# ECAT_SWITCH.net
KiCad netlist of a schematic drawn in Altium Designer
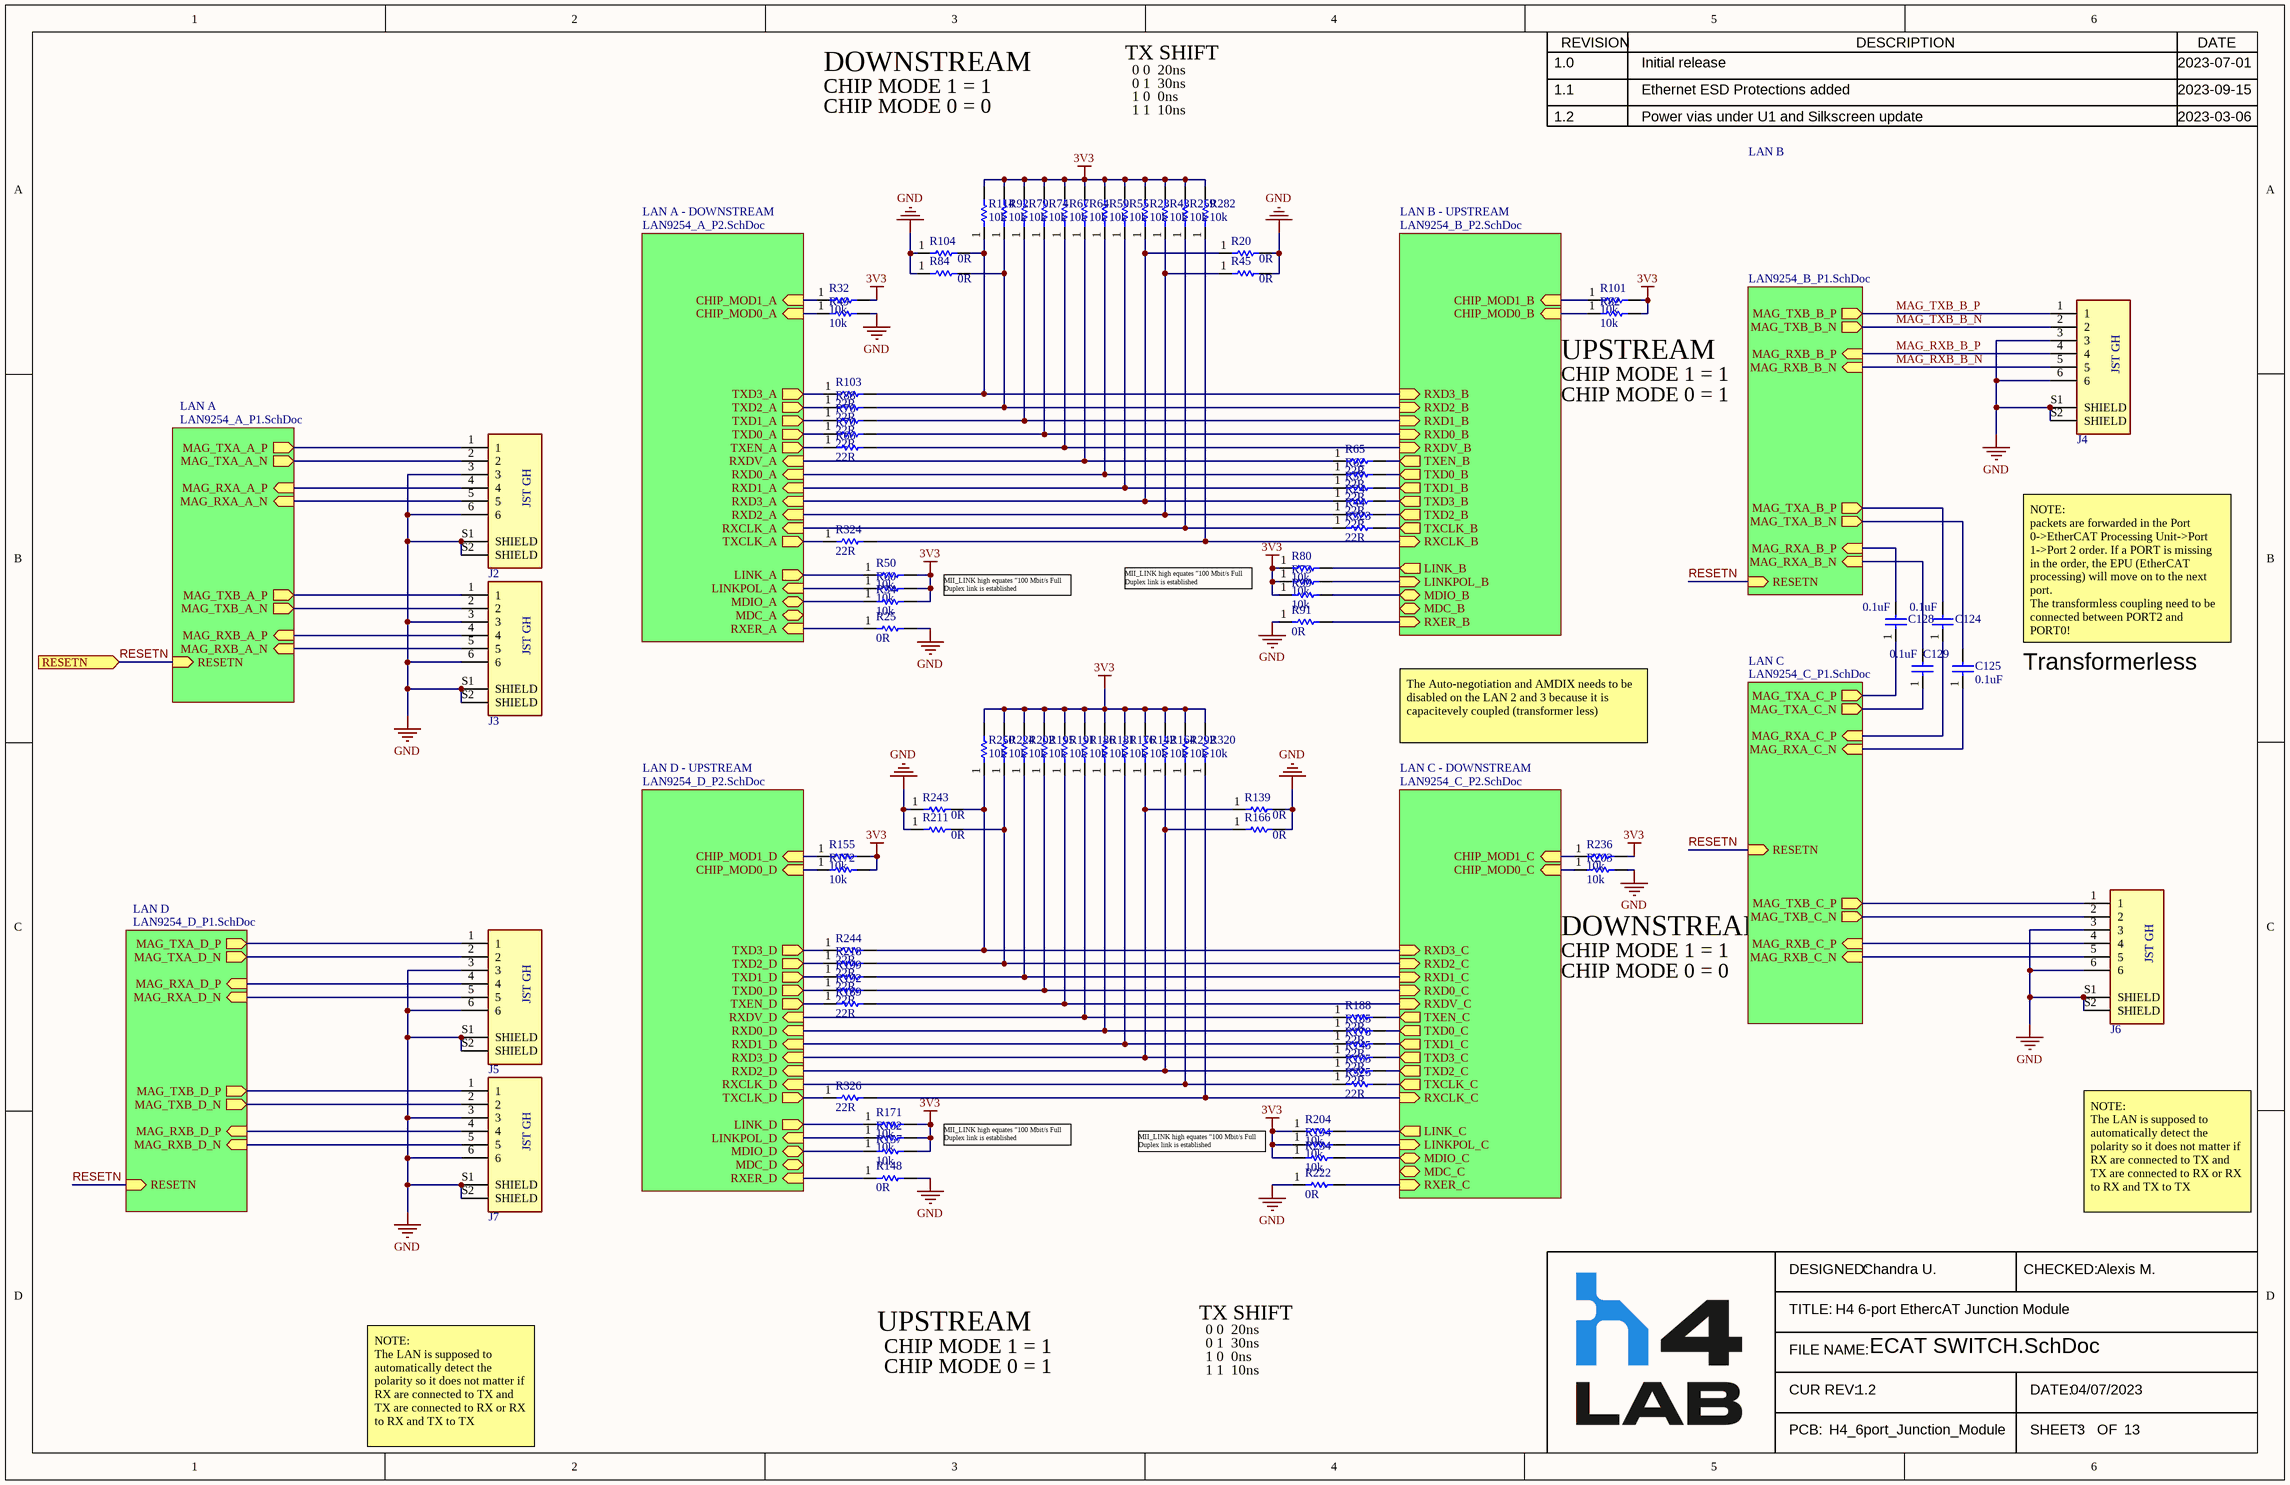
[diagram p0: ECAT SWITCH.SchDoc]

(export (version "E")
  (design (tool "Eeschema 10.0.6"))
  (components
    (comp (ref "C124")
      (value "0.1uF")
      (footprint "CAPC1608X09N(0603)")
      (description "CAP CER 0.1UF 100V X7R 0603")
      (fields (field (name "MPN") "CL10B104KC8NNNC") (field (name "TOLERANCE") "10%"))
      (libsource (lib "IHMC_Altium_Lib") (part "0.1uF_100V_0603_CAP"))
    )
    (comp (ref "C125")
      (value "0.1uF")
      (footprint "CAPC1608X09N(0603)")
      (description "CAP CER 0.1UF 100V X7R 0603")
      (fields (field (name "MPN") "CL10B104KC8NNNC") (field (name "TOLERANCE") "10%"))
      (libsource (lib "IHMC_Altium_Lib") (part "0.1uF_100V_0603_CAP"))
    )
    (comp (ref "C128")
      (value "0.1uF")
      (footprint "CAPC1608X09N(0603)")
      (description "CAP CER 0.1UF 100V X7R 0603")
      (fields (field (name "MPN") "CL10B104KC8NNNC") (field (name "TOLERANCE") "10%"))
      (libsource (lib "IHMC_Altium_Lib") (part "0.1uF_100V_0603_CAP"))
    )
    (comp (ref "C129")
      (value "0.1uF")
      (footprint "CAPC1608X09N(0603)")
      (description "CAP CER 0.1UF 100V X7R 0603")
      (fields (field (name "MPN") "CL10B104KC8NNNC") (field (name "TOLERANCE") "10%"))
      (libsource (lib "IHMC_Altium_Lib") (part "0.1uF_100V_0603_CAP"))
    )
    (comp (ref "J2")
      (value "BM06B-GHS-TBT")
      (footprint "JST_GH_6POS_STRAI")
      (description "CONN HEADER GH TOP 6POS 1.25MM")
      (fields
        (field (name "MANUFACTURER") "JST")
        (field (name "MANUFACTURER PART NUMBER") "BM06B-GHS-TBT(LF)(SN)(N)")
      )
      (libsource (lib "IHMC_Altium_Lib") (part "BM06B-GHS-TBT_JST_6POS_1.25MM_CON"))
    )
    (comp (ref "J3")
      (value "BM06B-GHS-TBT")
      (footprint "JST_GH_6POS_STRAI")
      (description "CONN HEADER GH TOP 6POS 1.25MM")
      (fields
        (field (name "MANUFACTURER") "JST")
        (field (name "MANUFACTURER PART NUMBER") "BM06B-GHS-TBT(LF)(SN)(N)")
      )
      (libsource (lib "IHMC_Altium_Lib") (part "BM06B-GHS-TBT_JST_6POS_1.25MM_CON"))
    )
    (comp (ref "J4")
      (value "BM06B-GHS-TBT")
      (footprint "JST_GH_6POS_STRAI")
      (description "CONN HEADER GH TOP 6POS 1.25MM")
      (fields
        (field (name "MANUFACTURER") "JST")
        (field (name "MANUFACTURER PART NUMBER") "BM06B-GHS-TBT(LF)(SN)(N)")
      )
      (libsource (lib "IHMC_Altium_Lib") (part "BM06B-GHS-TBT_JST_6POS_1.25MM_CON"))
    )
    (comp (ref "J5")
      (value "BM06B-GHS-TBT")
      (footprint "JST_GH_6POS_STRAI")
      (description "CONN HEADER GH TOP 6POS 1.25MM")
      (fields
        (field (name "MANUFACTURER") "JST")
        (field (name "MANUFACTURER PART NUMBER") "BM06B-GHS-TBT(LF)(SN)(N)")
      )
      (libsource (lib "IHMC_Altium_Lib") (part "BM06B-GHS-TBT_JST_6POS_1.25MM_CON"))
    )
    (comp (ref "J6")
      (value "BM06B-GHS-TBT")
      (footprint "JST_GH_6POS_STRAI")
      (description "CONN HEADER GH TOP 6POS 1.25MM")
      (fields
        (field (name "MANUFACTURER") "JST")
        (field (name "MANUFACTURER PART NUMBER") "BM06B-GHS-TBT(LF)(SN)(N)")
      )
      (libsource (lib "IHMC_Altium_Lib") (part "BM06B-GHS-TBT_JST_6POS_1.25MM_CON"))
    )
    (comp (ref "J7")
      (value "BM06B-GHS-TBT")
      (footprint "JST_GH_6POS_STRAI")
      (description "CONN HEADER GH TOP 6POS 1.25MM")
      (fields
        (field (name "MANUFACTURER") "JST")
        (field (name "MANUFACTURER PART NUMBER") "BM06B-GHS-TBT(LF)(SN)(N)")
      )
      (libsource (lib "IHMC_Altium_Lib") (part "BM06B-GHS-TBT_JST_6POS_1.25MM_CON"))
    )
    (comp (ref "R20")
      (value "0R")
      (footprint "RESC1608X09N(0603)")
      (description "RES SMD 0 OHM JUMPER 1/10W 0603")
      (fields (field (name "MPN") "RC0603JR-070RL") (field (name "TOLERANCE") "Jumper"))
      (libsource (lib "H4_6-port_EtherCAT_Junction_Module") (part "0R_1/10W_0603_RES"))
    )
    (comp (ref "R23")
      (value "10k")
      (footprint "RESC1005X06N(0402)")
      (description "RES SMD 10K OHM 1% 1/16W 0402")
      (fields (field (name "MPN") "RC0402FR-0710KL") (field (name "TOLERANCE") "1%"))
      (libsource (lib "IHMC_Resistors") (part "10k_1/16W_0402_RES"))
    )
    (comp (ref "R24")
      (value "22R")
      (footprint "0402")
      (description "Res Thick Film 0402 22 Ohm 1% 0.125W(1/8W) ±200ppm/C Pad SMD T/R")
      (fields
        (field (name "MANUFACTURER") "TE Connectivity")
        (field (name "MANUFACTURER PART NUMBER") "CRGP0402F22R")
      )
      (libsource (lib "IHMC_Resistors") (part "22R_1/8W_1%_0402_CRGP0402F22R_RES"))
    )
    (comp (ref "R25")
      (value "0R")
      (footprint "0402")
      (fields
        (field (name "MANUFACTURER") "Vishay Dale")
        (field (name "MANUFACTURER PART NUMBER") "RCS04020000Z0ED")
      )
      (libsource (lib "IHMC_Altium_Lib") (part "0R_1/5W_0402_RCS04020000Z0ED_RES"))
    )
    (comp (ref "R32")
      (value "10k")
      (footprint "RESC1005X06N(0402)")
      (description "RES SMD 10K OHM 1% 1/16W 0402")
      (fields (field (name "MPN") "RC0402FR-0710KL") (field (name "TOLERANCE") "1%"))
      (libsource (lib "IHMC_Resistors") (part "10k_1/16W_0402_RES"))
    )
    (comp (ref "R34")
      (value "10k")
      (footprint "RESC1005X06N(0402)")
      (description "RES SMD 10K OHM 1% 1/16W 0402")
      (fields (field (name "MPN") "RC0402FR-0710KL") (field (name "TOLERANCE") "1%"))
      (libsource (lib "IHMC_Resistors") (part "10k_1/16W_0402_RES"))
    )
    (comp (ref "R43")
      (value "10k")
      (footprint "RESC1005X06N(0402)")
      (description "RES SMD 10K OHM 1% 1/16W 0402")
      (fields (field (name "MPN") "RC0402FR-0710KL") (field (name "TOLERANCE") "1%"))
      (libsource (lib "IHMC_Resistors") (part "10k_1/16W_0402_RES"))
    )
    (comp (ref "R44")
      (value "22R")
      (footprint "0402")
      (description "Res Thick Film 0402 22 Ohm 1% 0.125W(1/8W) ±200ppm/C Pad SMD T/R")
      (fields
        (field (name "MANUFACTURER") "TE Connectivity")
        (field (name "MANUFACTURER PART NUMBER") "CRGP0402F22R")
      )
      (libsource (lib "IHMC_Resistors") (part "22R_1/8W_1%_0402_CRGP0402F22R_RES"))
    )
    (comp (ref "R45")
      (value "0R")
      (footprint "RESC1608X09N(0603)")
      (description "RES SMD 0 OHM JUMPER 1/10W 0603")
      (fields (field (name "MPN") "RC0603JR-070RL") (field (name "TOLERANCE") "Jumper"))
      (libsource (lib "H4_6-port_EtherCAT_Junction_Module") (part "0R_1/10W_0603_RES"))
    )
    (comp (ref "R49")
      (value "10k")
      (footprint "RESC1005X06N(0402)")
      (description "RES SMD 10K OHM 1% 1/16W 0402")
      (fields (field (name "MPN") "RC0402FR-0710KL") (field (name "TOLERANCE") "1%"))
      (libsource (lib "IHMC_Resistors") (part "10k_1/16W_0402_RES"))
    )
    (comp (ref "R50")
      (value "10k")
      (footprint "RESC1005X06N(0402)")
      (description "RES SMD 10K OHM 1% 1/16W 0402")
      (fields (field (name "MPN") "RC0402FR-0710KL") (field (name "TOLERANCE") "1%"))
      (libsource (lib "IHMC_Resistors") (part "10k_1/16W_0402_RES"))
    )
    (comp (ref "R55")
      (value "10k")
      (footprint "RESC1005X06N(0402)")
      (description "RES SMD 10K OHM 1% 1/16W 0402")
      (fields (field (name "MPN") "RC0402FR-0710KL") (field (name "TOLERANCE") "1%"))
      (libsource (lib "IHMC_Resistors") (part "10k_1/16W_0402_RES"))
    )
    (comp (ref "R57")
      (value "22R")
      (footprint "0402")
      (description "Res Thick Film 0402 22 Ohm 1% 0.125W(1/8W) ±200ppm/C Pad SMD T/R")
      (fields
        (field (name "MANUFACTURER") "TE Connectivity")
        (field (name "MANUFACTURER PART NUMBER") "CRGP0402F22R")
      )
      (libsource (lib "IHMC_Resistors") (part "22R_1/8W_1%_0402_CRGP0402F22R_RES"))
    )
    (comp (ref "R59")
      (value "10k")
      (footprint "RESC1005X06N(0402)")
      (description "RES SMD 10K OHM 1% 1/16W 0402")
      (fields (field (name "MPN") "RC0402FR-0710KL") (field (name "TOLERANCE") "1%"))
      (libsource (lib "IHMC_Resistors") (part "10k_1/16W_0402_RES"))
    )
    (comp (ref "R60")
      (value "10k")
      (footprint "RESC1005X06N(0402)")
      (description "RES SMD 10K OHM 1% 1/16W 0402")
      (fields (field (name "MPN") "RC0402FR-0710KL") (field (name "TOLERANCE") "1%"))
      (libsource (lib "IHMC_Resistors") (part "10k_1/16W_0402_RES"))
    )
    (comp (ref "R62")
      (value "22R")
      (footprint "0402")
      (description "Res Thick Film 0402 22 Ohm 1% 0.125W(1/8W) ±200ppm/C Pad SMD T/R")
      (fields
        (field (name "MANUFACTURER") "TE Connectivity")
        (field (name "MANUFACTURER PART NUMBER") "CRGP0402F22R")
      )
      (libsource (lib "IHMC_Resistors") (part "22R_1/8W_1%_0402_CRGP0402F22R_RES"))
    )
    (comp (ref "R64")
      (value "10k")
      (footprint "RESC1005X06N(0402)")
      (description "RES SMD 10K OHM 1% 1/16W 0402")
      (fields (field (name "MPN") "RC0402FR-0710KL") (field (name "TOLERANCE") "1%"))
      (libsource (lib "IHMC_Resistors") (part "10k_1/16W_0402_RES"))
    )
    (comp (ref "R65")
      (value "22R")
      (footprint "0402")
      (description "Res Thick Film 0402 22 Ohm 1% 0.125W(1/8W) ±200ppm/C Pad SMD T/R")
      (fields
        (field (name "MANUFACTURER") "TE Connectivity")
        (field (name "MANUFACTURER PART NUMBER") "CRGP0402F22R")
      )
      (libsource (lib "IHMC_Resistors") (part "22R_1/8W_1%_0402_CRGP0402F22R_RES"))
    )
    (comp (ref "R66")
      (value "22R")
      (footprint "0402")
      (description "Res Thick Film 0402 22 Ohm 1% 0.125W(1/8W) ±200ppm/C Pad SMD T/R")
      (fields
        (field (name "MANUFACTURER") "TE Connectivity")
        (field (name "MANUFACTURER PART NUMBER") "CRGP0402F22R")
      )
      (libsource (lib "IHMC_Resistors") (part "22R_1/8W_1%_0402_CRGP0402F22R_RES"))
    )
    (comp (ref "R67")
      (value "10k")
      (footprint "RESC1005X06N(0402)")
      (description "RES SMD 10K OHM 1% 1/16W 0402")
      (fields (field (name "MPN") "RC0402FR-0710KL") (field (name "TOLERANCE") "1%"))
      (libsource (lib "IHMC_Resistors") (part "10k_1/16W_0402_RES"))
    )
    (comp (ref "R70")
      (value "22R")
      (footprint "0402")
      (description "Res Thick Film 0402 22 Ohm 1% 0.125W(1/8W) ±200ppm/C Pad SMD T/R")
      (fields
        (field (name "MANUFACTURER") "TE Connectivity")
        (field (name "MANUFACTURER PART NUMBER") "CRGP0402F22R")
      )
      (libsource (lib "IHMC_Resistors") (part "22R_1/8W_1%_0402_CRGP0402F22R_RES"))
    )
    (comp (ref "R73")
      (value "10k")
      (footprint "RESC1005X06N(0402)")
      (description "RES SMD 10K OHM 1% 1/16W 0402")
      (fields (field (name "MPN") "RC0402FR-0710KL") (field (name "TOLERANCE") "1%"))
      (libsource (lib "IHMC_Resistors") (part "10k_1/16W_0402_RES"))
    )
    (comp (ref "R74")
      (value "10k")
      (footprint "RESC1005X06N(0402)")
      (description "RES SMD 10K OHM 1% 1/16W 0402")
      (fields (field (name "MPN") "RC0402FR-0710KL") (field (name "TOLERANCE") "1%"))
      (libsource (lib "IHMC_Resistors") (part "10k_1/16W_0402_RES"))
    )
    (comp (ref "R76")
      (value "22R")
      (footprint "0402")
      (description "Res Thick Film 0402 22 Ohm 1% 0.125W(1/8W) ±200ppm/C Pad SMD T/R")
      (fields
        (field (name "MANUFACTURER") "TE Connectivity")
        (field (name "MANUFACTURER PART NUMBER") "CRGP0402F22R")
      )
      (libsource (lib "IHMC_Resistors") (part "22R_1/8W_1%_0402_CRGP0402F22R_RES"))
    )
    (comp (ref "R79")
      (value "10k")
      (footprint "RESC1005X06N(0402)")
      (description "RES SMD 10K OHM 1% 1/16W 0402")
      (fields (field (name "MPN") "RC0402FR-0710KL") (field (name "TOLERANCE") "1%"))
      (libsource (lib "IHMC_Resistors") (part "10k_1/16W_0402_RES"))
    )
    (comp (ref "R80")
      (value "10k")
      (footprint "RESC1005X06N(0402)")
      (description "RES SMD 10K OHM 1% 1/16W 0402")
      (fields (field (name "MPN") "RC0402FR-0710KL") (field (name "TOLERANCE") "1%"))
      (libsource (lib "IHMC_Resistors") (part "10k_1/16W_0402_RES"))
    )
    (comp (ref "R82")
      (value "10k")
      (footprint "RESC1005X06N(0402)")
      (description "RES SMD 10K OHM 1% 1/16W 0402")
      (fields (field (name "MPN") "RC0402FR-0710KL") (field (name "TOLERANCE") "1%"))
      (libsource (lib "IHMC_Resistors") (part "10k_1/16W_0402_RES"))
    )
    (comp (ref "R84")
      (value "0R")
      (footprint "RESC1608X09N(0603)")
      (description "RES SMD 0 OHM JUMPER 1/10W 0603")
      (fields (field (name "MPN") "RC0603JR-070RL") (field (name "TOLERANCE") "Jumper"))
      (libsource (lib "H4_6-port_EtherCAT_Junction_Module") (part "0R_1/10W_0603_RES"))
    )
    (comp (ref "R88")
      (value "22R")
      (footprint "0402")
      (description "Res Thick Film 0402 22 Ohm 1% 0.125W(1/8W) ±200ppm/C Pad SMD T/R")
      (fields
        (field (name "MANUFACTURER") "TE Connectivity")
        (field (name "MANUFACTURER PART NUMBER") "CRGP0402F22R")
      )
      (libsource (lib "IHMC_Resistors") (part "22R_1/8W_1%_0402_CRGP0402F22R_RES"))
    )
    (comp (ref "R91")
      (value "0R")
      (footprint "0402")
      (fields
        (field (name "MANUFACTURER") "Vishay Dale")
        (field (name "MANUFACTURER PART NUMBER") "RCS04020000Z0ED")
      )
      (libsource (lib "IHMC_Altium_Lib") (part "0R_1/5W_0402_RCS04020000Z0ED_RES"))
    )
    (comp (ref "R92")
      (value "10k")
      (footprint "RESC1005X06N(0402)")
      (description "RES SMD 10K OHM 1% 1/16W 0402")
      (fields (field (name "MPN") "RC0402FR-0710KL") (field (name "TOLERANCE") "1%"))
      (libsource (lib "IHMC_Resistors") (part "10k_1/16W_0402_RES"))
    )
    (comp (ref "R99")
      (value "10k")
      (footprint "RESC1005X06N(0402)")
      (description "RES SMD 10K OHM 1% 1/16W 0402")
      (fields (field (name "MPN") "RC0402FR-0710KL") (field (name "TOLERANCE") "1%"))
      (libsource (lib "IHMC_Resistors") (part "10k_1/16W_0402_RES"))
    )
    (comp (ref "R101")
      (value "10k")
      (footprint "RESC1005X06N(0402)")
      (description "RES SMD 10K OHM 1% 1/16W 0402")
      (fields (field (name "MPN") "RC0402FR-0710KL") (field (name "TOLERANCE") "1%"))
      (libsource (lib "IHMC_Resistors") (part "10k_1/16W_0402_RES"))
    )
    (comp (ref "R103")
      (value "22R")
      (footprint "0402")
      (description "Res Thick Film 0402 22 Ohm 1% 0.125W(1/8W) ±200ppm/C Pad SMD T/R")
      (fields
        (field (name "MANUFACTURER") "TE Connectivity")
        (field (name "MANUFACTURER PART NUMBER") "CRGP0402F22R")
      )
      (libsource (lib "IHMC_Resistors") (part "22R_1/8W_1%_0402_CRGP0402F22R_RES"))
    )
    (comp (ref "R104")
      (value "0R")
      (footprint "RESC1608X09N(0603)")
      (description "RES SMD 0 OHM JUMPER 1/10W 0603")
      (fields (field (name "MPN") "RC0603JR-070RL") (field (name "TOLERANCE") "Jumper"))
      (libsource (lib "H4_6-port_EtherCAT_Junction_Module") (part "0R_1/10W_0603_RES"))
    )
    (comp (ref "R114")
      (value "10k")
      (footprint "RESC1005X06N(0402)")
      (description "RES SMD 10K OHM 1% 1/16W 0402")
      (fields (field (name "MPN") "RC0402FR-0710KL") (field (name "TOLERANCE") "1%"))
      (libsource (lib "IHMC_Resistors") (part "10k_1/16W_0402_RES"))
    )
    (comp (ref "R139")
      (value "0R")
      (footprint "RESC1608X09N(0603)")
      (description "RES SMD 0 OHM JUMPER 1/10W 0603")
      (fields (field (name "MPN") "RC0603JR-070RL") (field (name "TOLERANCE") "Jumper"))
      (libsource (lib "H4_6-port_EtherCAT_Junction_Module") (part "0R_1/10W_0603_RES"))
    )
    (comp (ref "R142")
      (value "10k")
      (footprint "RESC1005X06N(0402)")
      (description "RES SMD 10K OHM 1% 1/16W 0402")
      (fields (field (name "MPN") "RC0402FR-0710KL") (field (name "TOLERANCE") "1%"))
      (libsource (lib "IHMC_Resistors") (part "10k_1/16W_0402_RES"))
    )
    (comp (ref "R145")
      (value "22R")
      (footprint "0402")
      (description "Res Thick Film 0402 22 Ohm 1% 0.125W(1/8W) ±200ppm/C Pad SMD T/R")
      (fields
        (field (name "MANUFACTURER") "TE Connectivity")
        (field (name "MANUFACTURER PART NUMBER") "CRGP0402F22R")
      )
      (libsource (lib "IHMC_Resistors") (part "22R_1/8W_1%_0402_CRGP0402F22R_RES"))
    )
    (comp (ref "R148")
      (value "0R")
      (footprint "0402")
      (fields
        (field (name "MANUFACTURER") "Vishay Dale")
        (field (name "MANUFACTURER PART NUMBER") "RCS04020000Z0ED")
      )
      (libsource (lib "IHMC_Altium_Lib") (part "0R_1/5W_0402_RCS04020000Z0ED_RES"))
    )
    (comp (ref "R155")
      (value "10k")
      (footprint "RESC1005X06N(0402)")
      (description "RES SMD 10K OHM 1% 1/16W 0402")
      (fields (field (name "MPN") "RC0402FR-0710KL") (field (name "TOLERANCE") "1%"))
      (libsource (lib "IHMC_Resistors") (part "10k_1/16W_0402_RES"))
    )
    (comp (ref "R157")
      (value "10k")
      (footprint "RESC1005X06N(0402)")
      (description "RES SMD 10K OHM 1% 1/16W 0402")
      (fields (field (name "MPN") "RC0402FR-0710KL") (field (name "TOLERANCE") "1%"))
      (libsource (lib "IHMC_Resistors") (part "10k_1/16W_0402_RES"))
    )
    (comp (ref "R164")
      (value "10k")
      (footprint "RESC1005X06N(0402)")
      (description "RES SMD 10K OHM 1% 1/16W 0402")
      (fields (field (name "MPN") "RC0402FR-0710KL") (field (name "TOLERANCE") "1%"))
      (libsource (lib "IHMC_Resistors") (part "10k_1/16W_0402_RES"))
    )
    (comp (ref "R165")
      (value "22R")
      (footprint "0402")
      (description "Res Thick Film 0402 22 Ohm 1% 0.125W(1/8W) ±200ppm/C Pad SMD T/R")
      (fields
        (field (name "MANUFACTURER") "TE Connectivity")
        (field (name "MANUFACTURER PART NUMBER") "CRGP0402F22R")
      )
      (libsource (lib "IHMC_Resistors") (part "22R_1/8W_1%_0402_CRGP0402F22R_RES"))
    )
    (comp (ref "R166")
      (value "0R")
      (footprint "RESC1608X09N(0603)")
      (description "RES SMD 0 OHM JUMPER 1/10W 0603")
      (fields (field (name "MPN") "RC0603JR-070RL") (field (name "TOLERANCE") "Jumper"))
      (libsource (lib "H4_6-port_EtherCAT_Junction_Module") (part "0R_1/10W_0603_RES"))
    )
    (comp (ref "R171")
      (value "10k")
      (footprint "RESC1005X06N(0402)")
      (description "RES SMD 10K OHM 1% 1/16W 0402")
      (fields (field (name "MPN") "RC0402FR-0710KL") (field (name "TOLERANCE") "1%"))
      (libsource (lib "IHMC_Resistors") (part "10k_1/16W_0402_RES"))
    )
    (comp (ref "R172")
      (value "10k")
      (footprint "RESC1005X06N(0402)")
      (description "RES SMD 10K OHM 1% 1/16W 0402")
      (fields (field (name "MPN") "RC0402FR-0710KL") (field (name "TOLERANCE") "1%"))
      (libsource (lib "IHMC_Resistors") (part "10k_1/16W_0402_RES"))
    )
    (comp (ref "R176")
      (value "10k")
      (footprint "RESC1005X06N(0402)")
      (description "RES SMD 10K OHM 1% 1/16W 0402")
      (fields (field (name "MPN") "RC0402FR-0710KL") (field (name "TOLERANCE") "1%"))
      (libsource (lib "IHMC_Resistors") (part "10k_1/16W_0402_RES"))
    )
    (comp (ref "R178")
      (value "22R")
      (footprint "0402")
      (description "Res Thick Film 0402 22 Ohm 1% 0.125W(1/8W) ±200ppm/C Pad SMD T/R")
      (fields
        (field (name "MANUFACTURER") "TE Connectivity")
        (field (name "MANUFACTURER PART NUMBER") "CRGP0402F22R")
      )
      (libsource (lib "IHMC_Resistors") (part "22R_1/8W_1%_0402_CRGP0402F22R_RES"))
    )
    (comp (ref "R181")
      (value "10k")
      (footprint "RESC1005X06N(0402)")
      (description "RES SMD 10K OHM 1% 1/16W 0402")
      (fields (field (name "MPN") "RC0402FR-0710KL") (field (name "TOLERANCE") "1%"))
      (libsource (lib "IHMC_Resistors") (part "10k_1/16W_0402_RES"))
    )
    (comp (ref "R182")
      (value "10k")
      (footprint "RESC1005X06N(0402)")
      (description "RES SMD 10K OHM 1% 1/16W 0402")
      (fields (field (name "MPN") "RC0402FR-0710KL") (field (name "TOLERANCE") "1%"))
      (libsource (lib "IHMC_Resistors") (part "10k_1/16W_0402_RES"))
    )
    (comp (ref "R185")
      (value "22R")
      (footprint "0402")
      (description "Res Thick Film 0402 22 Ohm 1% 0.125W(1/8W) ±200ppm/C Pad SMD T/R")
      (fields
        (field (name "MANUFACTURER") "TE Connectivity")
        (field (name "MANUFACTURER PART NUMBER") "CRGP0402F22R")
      )
      (libsource (lib "IHMC_Resistors") (part "22R_1/8W_1%_0402_CRGP0402F22R_RES"))
    )
    (comp (ref "R186")
      (value "10k")
      (footprint "RESC1005X06N(0402)")
      (description "RES SMD 10K OHM 1% 1/16W 0402")
      (fields (field (name "MPN") "RC0402FR-0710KL") (field (name "TOLERANCE") "1%"))
      (libsource (lib "IHMC_Resistors") (part "10k_1/16W_0402_RES"))
    )
    (comp (ref "R188")
      (value "22R")
      (footprint "0402")
      (description "Res Thick Film 0402 22 Ohm 1% 0.125W(1/8W) ±200ppm/C Pad SMD T/R")
      (fields
        (field (name "MANUFACTURER") "TE Connectivity")
        (field (name "MANUFACTURER PART NUMBER") "CRGP0402F22R")
      )
      (libsource (lib "IHMC_Resistors") (part "22R_1/8W_1%_0402_CRGP0402F22R_RES"))
    )
    (comp (ref "R189")
      (value "22R")
      (footprint "0402")
      (description "Res Thick Film 0402 22 Ohm 1% 0.125W(1/8W) ±200ppm/C Pad SMD T/R")
      (fields
        (field (name "MANUFACTURER") "TE Connectivity")
        (field (name "MANUFACTURER PART NUMBER") "CRGP0402F22R")
      )
      (libsource (lib "IHMC_Resistors") (part "22R_1/8W_1%_0402_CRGP0402F22R_RES"))
    )
    (comp (ref "R191")
      (value "10k")
      (footprint "RESC1005X06N(0402)")
      (description "RES SMD 10K OHM 1% 1/16W 0402")
      (fields (field (name "MPN") "RC0402FR-0710KL") (field (name "TOLERANCE") "1%"))
      (libsource (lib "IHMC_Resistors") (part "10k_1/16W_0402_RES"))
    )
    (comp (ref "R192")
      (value "22R")
      (footprint "0402")
      (description "Res Thick Film 0402 22 Ohm 1% 0.125W(1/8W) ±200ppm/C Pad SMD T/R")
      (fields
        (field (name "MANUFACTURER") "TE Connectivity")
        (field (name "MANUFACTURER PART NUMBER") "CRGP0402F22R")
      )
      (libsource (lib "IHMC_Resistors") (part "22R_1/8W_1%_0402_CRGP0402F22R_RES"))
    )
    (comp (ref "R194")
      (value "10k")
      (footprint "RESC1005X06N(0402)")
      (description "RES SMD 10K OHM 1% 1/16W 0402")
      (fields (field (name "MPN") "RC0402FR-0710KL") (field (name "TOLERANCE") "1%"))
      (libsource (lib "IHMC_Resistors") (part "10k_1/16W_0402_RES"))
    )
    (comp (ref "R195")
      (value "10k")
      (footprint "RESC1005X06N(0402)")
      (description "RES SMD 10K OHM 1% 1/16W 0402")
      (fields (field (name "MPN") "RC0402FR-0710KL") (field (name "TOLERANCE") "1%"))
      (libsource (lib "IHMC_Resistors") (part "10k_1/16W_0402_RES"))
    )
    (comp (ref "R199")
      (value "22R")
      (footprint "0402")
      (description "Res Thick Film 0402 22 Ohm 1% 0.125W(1/8W) ±200ppm/C Pad SMD T/R")
      (fields
        (field (name "MANUFACTURER") "TE Connectivity")
        (field (name "MANUFACTURER PART NUMBER") "CRGP0402F22R")
      )
      (libsource (lib "IHMC_Resistors") (part "22R_1/8W_1%_0402_CRGP0402F22R_RES"))
    )
    (comp (ref "R202")
      (value "10k")
      (footprint "RESC1005X06N(0402)")
      (description "RES SMD 10K OHM 1% 1/16W 0402")
      (fields (field (name "MPN") "RC0402FR-0710KL") (field (name "TOLERANCE") "1%"))
      (libsource (lib "IHMC_Resistors") (part "10k_1/16W_0402_RES"))
    )
    (comp (ref "R203")
      (value "10k")
      (footprint "RESC1005X06N(0402)")
      (description "RES SMD 10K OHM 1% 1/16W 0402")
      (fields (field (name "MPN") "RC0402FR-0710KL") (field (name "TOLERANCE") "1%"))
      (libsource (lib "IHMC_Resistors") (part "10k_1/16W_0402_RES"))
    )
    (comp (ref "R204")
      (value "10k")
      (footprint "RESC1005X06N(0402)")
      (description "RES SMD 10K OHM 1% 1/16W 0402")
      (fields (field (name "MPN") "RC0402FR-0710KL") (field (name "TOLERANCE") "1%"))
      (libsource (lib "IHMC_Resistors") (part "10k_1/16W_0402_RES"))
    )
    (comp (ref "R211")
      (value "0R")
      (footprint "RESC1608X09N(0603)")
      (description "RES SMD 0 OHM JUMPER 1/10W 0603")
      (fields (field (name "MPN") "RC0603JR-070RL") (field (name "TOLERANCE") "Jumper"))
      (libsource (lib "H4_6-port_EtherCAT_Junction_Module") (part "0R_1/10W_0603_RES"))
    )
    (comp (ref "R218")
      (value "22R")
      (footprint "0402")
      (description "Res Thick Film 0402 22 Ohm 1% 0.125W(1/8W) ±200ppm/C Pad SMD T/R")
      (fields
        (field (name "MANUFACTURER") "TE Connectivity")
        (field (name "MANUFACTURER PART NUMBER") "CRGP0402F22R")
      )
      (libsource (lib "IHMC_Resistors") (part "22R_1/8W_1%_0402_CRGP0402F22R_RES"))
    )
    (comp (ref "R222")
      (value "0R")
      (footprint "0402")
      (fields
        (field (name "MANUFACTURER") "Vishay Dale")
        (field (name "MANUFACTURER PART NUMBER") "RCS04020000Z0ED")
      )
      (libsource (lib "IHMC_Altium_Lib") (part "0R_1/5W_0402_RCS04020000Z0ED_RES"))
    )
    (comp (ref "R224")
      (value "10k")
      (footprint "RESC1005X06N(0402)")
      (description "RES SMD 10K OHM 1% 1/16W 0402")
      (fields (field (name "MPN") "RC0402FR-0710KL") (field (name "TOLERANCE") "1%"))
      (libsource (lib "IHMC_Resistors") (part "10k_1/16W_0402_RES"))
    )
    (comp (ref "R234")
      (value "10k")
      (footprint "RESC1005X06N(0402)")
      (description "RES SMD 10K OHM 1% 1/16W 0402")
      (fields (field (name "MPN") "RC0402FR-0710KL") (field (name "TOLERANCE") "1%"))
      (libsource (lib "IHMC_Resistors") (part "10k_1/16W_0402_RES"))
    )
    (comp (ref "R236")
      (value "10k")
      (footprint "RESC1005X06N(0402)")
      (description "RES SMD 10K OHM 1% 1/16W 0402")
      (fields (field (name "MPN") "RC0402FR-0710KL") (field (name "TOLERANCE") "1%"))
      (libsource (lib "IHMC_Resistors") (part "10k_1/16W_0402_RES"))
    )
    (comp (ref "R243")
      (value "0R")
      (footprint "RESC1608X09N(0603)")
      (description "RES SMD 0 OHM JUMPER 1/10W 0603")
      (fields (field (name "MPN") "RC0603JR-070RL") (field (name "TOLERANCE") "Jumper"))
      (libsource (lib "H4_6-port_EtherCAT_Junction_Module") (part "0R_1/10W_0603_RES"))
    )
    (comp (ref "R244")
      (value "22R")
      (footprint "0402")
      (description "Res Thick Film 0402 22 Ohm 1% 0.125W(1/8W) ±200ppm/C Pad SMD T/R")
      (fields
        (field (name "MANUFACTURER") "TE Connectivity")
        (field (name "MANUFACTURER PART NUMBER") "CRGP0402F22R")
      )
      (libsource (lib "IHMC_Resistors") (part "22R_1/8W_1%_0402_CRGP0402F22R_RES"))
    )
    (comp (ref "R250")
      (value "10k")
      (footprint "RESC1005X06N(0402)")
      (description "RES SMD 10K OHM 1% 1/16W 0402")
      (fields (field (name "MPN") "RC0402FR-0710KL") (field (name "TOLERANCE") "1%"))
      (libsource (lib "IHMC_Resistors") (part "10k_1/16W_0402_RES"))
    )
    (comp (ref "R259")
      (value "10k")
      (footprint "RESC1005X06N(0402)")
      (description "RES SMD 10K OHM 1% 1/16W 0402")
      (fields (field (name "MPN") "RC0402FR-0710KL") (field (name "TOLERANCE") "1%"))
      (libsource (lib "IHMC_Resistors") (part "10k_1/16W_0402_RES"))
    )
    (comp (ref "R282")
      (value "10k")
      (footprint "RESC1005X06N(0402)")
      (description "RES SMD 10K OHM 1% 1/16W 0402")
      (fields (field (name "MPN") "RC0402FR-0710KL") (field (name "TOLERANCE") "1%"))
      (libsource (lib "IHMC_Resistors") (part "10k_1/16W_0402_RES"))
    )
    (comp (ref "R292")
      (value "10k")
      (footprint "RESC1005X06N(0402)")
      (description "RES SMD 10K OHM 1% 1/16W 0402")
      (fields (field (name "MPN") "RC0402FR-0710KL") (field (name "TOLERANCE") "1%"))
      (libsource (lib "IHMC_Resistors") (part "10k_1/16W_0402_RES"))
    )
    (comp (ref "R320")
      (value "10k")
      (footprint "RESC1005X06N(0402)")
      (description "RES SMD 10K OHM 1% 1/16W 0402")
      (fields (field (name "MPN") "RC0402FR-0710KL") (field (name "TOLERANCE") "1%"))
      (libsource (lib "IHMC_Resistors") (part "10k_1/16W_0402_RES"))
    )
    (comp (ref "R323")
      (value "22R")
      (footprint "0402")
      (description "Res Thick Film 0402 22 Ohm 1% 0.125W(1/8W) ±200ppm/C Pad SMD T/R")
      (fields
        (field (name "MANUFACTURER") "TE Connectivity")
        (field (name "MANUFACTURER PART NUMBER") "CRGP0402F22R")
      )
      (libsource (lib "IHMC_Resistors") (part "22R_1/8W_1%_0402_CRGP0402F22R_RES"))
    )
    (comp (ref "R324")
      (value "22R")
      (footprint "0402")
      (description "Res Thick Film 0402 22 Ohm 1% 0.125W(1/8W) ±200ppm/C Pad SMD T/R")
      (fields
        (field (name "MANUFACTURER") "TE Connectivity")
        (field (name "MANUFACTURER PART NUMBER") "CRGP0402F22R")
      )
      (libsource (lib "IHMC_Resistors") (part "22R_1/8W_1%_0402_CRGP0402F22R_RES"))
    )
    (comp (ref "R325")
      (value "22R")
      (footprint "0402")
      (description "Res Thick Film 0402 22 Ohm 1% 0.125W(1/8W) ±200ppm/C Pad SMD T/R")
      (fields
        (field (name "MANUFACTURER") "TE Connectivity")
        (field (name "MANUFACTURER PART NUMBER") "CRGP0402F22R")
      )
      (libsource (lib "IHMC_Resistors") (part "22R_1/8W_1%_0402_CRGP0402F22R_RES"))
    )
    (comp (ref "R326")
      (value "22R")
      (footprint "0402")
      (description "Res Thick Film 0402 22 Ohm 1% 0.125W(1/8W) ±200ppm/C Pad SMD T/R")
      (fields
        (field (name "MANUFACTURER") "TE Connectivity")
        (field (name "MANUFACTURER PART NUMBER") "CRGP0402F22R")
      )
      (libsource (lib "IHMC_Resistors") (part "22R_1/8W_1%_0402_CRGP0402F22R_RES"))
    )
  )
  (nets
    (net (code "1") (name "/CHIP_MOD0_A") (class "Default")
      (node (ref "R49") (pin "1") (pinfunction "1_1") (pintype "passive"))
    )
    (net (code "2") (name "/CHIP_MOD0_B") (class "Default")
      (node (ref "R82") (pin "1") (pinfunction "1_1") (pintype "passive"))
    )
    (net (code "3") (name "/CHIP_MOD0_C") (class "Default")
      (node (ref "R203") (pin "1") (pinfunction "1_1") (pintype "passive"))
    )
    (net (code "4") (name "/CHIP_MOD0_D") (class "Default")
      (node (ref "R172") (pin "1") (pinfunction "1_1") (pintype "passive"))
    )
    (net (code "5") (name "/CHIP_MOD1_A") (class "Default")
      (node (ref "R32") (pin "1") (pinfunction "1_1") (pintype "passive"))
    )
    (net (code "6") (name "/CHIP_MOD1_B") (class "Default")
      (node (ref "R101") (pin "1") (pinfunction "1_1") (pintype "passive"))
    )
    (net (code "7") (name "/CHIP_MOD1_C") (class "Default")
      (node (ref "R236") (pin "1") (pinfunction "1_1") (pintype "passive"))
    )
    (net (code "8") (name "/CHIP_MOD1_D") (class "Default")
      (node (ref "R155") (pin "1") (pinfunction "1_1") (pintype "passive"))
    )
    (net (code "9") (name "/LINKPOL_A") (class "Default")
      (node (ref "R60") (pin "1") (pinfunction "1_1") (pintype "passive"))
    )
    (net (code "10") (name "/LINKPOL_B") (class "Default")
      (node (ref "R73") (pin "2") (pinfunction "2_2") (pintype "passive"))
    )
    (net (code "11") (name "/LINKPOL_C") (class "Default")
      (node (ref "R194") (pin "2") (pinfunction "2_2") (pintype "passive"))
    )
    (net (code "12") (name "/LINKPOL_D") (class "Default")
      (node (ref "R182") (pin "1") (pinfunction "1_1") (pintype "passive"))
    )
    (net (code "13") (name "/LINK_A") (class "Default")
      (node (ref "R50") (pin "1") (pinfunction "1_1") (pintype "passive"))
    )
    (net (code "14") (name "/LINK_B") (class "Default")
      (node (ref "R80") (pin "2") (pinfunction "2_2") (pintype "passive"))
    )
    (net (code "15") (name "/LINK_C") (class "Default")
      (node (ref "R204") (pin "2") (pinfunction "2_2") (pintype "passive"))
    )
    (net (code "16") (name "/LINK_D") (class "Default")
      (node (ref "R171") (pin "1") (pinfunction "1_1") (pintype "passive"))
    )
    (net (code "17") (name "/MAG_RXA_A_N") (class "Default")
      (node (ref "J2") (pin "5") (pinfunction "5_5") (pintype "passive"))
    )
    (net (code "18") (name "/MAG_RXA_A_P") (class "Default")
      (node (ref "J2") (pin "4") (pinfunction "4_4") (pintype "passive"))
    )
    (net (code "19") (name "/MAG_RXA_B_N") (class "Default")
      (node (ref "C129") (pin "2") (pinfunction "2_2") (pintype "passive"))
    )
    (net (code "20") (name "/MAG_RXA_B_P") (class "Default")
      (node (ref "C128") (pin "2") (pinfunction "2_2") (pintype "passive"))
    )
    (net (code "21") (name "/MAG_RXA_C_N") (class "Default")
      (node (ref "C125") (pin "1") (pinfunction "1_1") (pintype "passive"))
    )
    (net (code "22") (name "/MAG_RXA_C_P") (class "Default")
      (node (ref "C124") (pin "1") (pinfunction "1_1") (pintype "passive"))
    )
    (net (code "23") (name "/MAG_RXA_D_N") (class "Default")
      (node (ref "J5") (pin "5") (pinfunction "5_5") (pintype "passive"))
    )
    (net (code "24") (name "/MAG_RXA_D_P") (class "Default")
      (node (ref "J5") (pin "4") (pinfunction "4_4") (pintype "passive"))
    )
    (net (code "25") (name "/MAG_RXB_A_N") (class "Default")
      (node (ref "J3") (pin "5") (pinfunction "5_5") (pintype "passive"))
    )
    (net (code "26") (name "/MAG_RXB_A_P") (class "Default")
      (node (ref "J3") (pin "4") (pinfunction "4_4") (pintype "passive"))
    )
    (net (code "27") (name "/MAG_RXB_B_N") (class "Default")
      (node (ref "J4") (pin "5") (pinfunction "5_5") (pintype "passive"))
    )
    (net (code "28") (name "/MAG_RXB_B_P") (class "Default")
      (node (ref "J4") (pin "4") (pinfunction "4_4") (pintype "passive"))
    )
    (net (code "29") (name "/MAG_RXB_C_N") (class "Default")
      (node (ref "J6") (pin "5") (pinfunction "5_5") (pintype "passive"))
    )
    (net (code "30") (name "/MAG_RXB_C_P") (class "Default")
      (node (ref "J6") (pin "4") (pinfunction "4_4") (pintype "passive"))
    )
    (net (code "31") (name "/MAG_RXB_D_N") (class "Default")
      (node (ref "J7") (pin "5") (pinfunction "5_5") (pintype "passive"))
    )
    (net (code "32") (name "/MAG_RXB_D_P") (class "Default")
      (node (ref "J7") (pin "4") (pinfunction "4_4") (pintype "passive"))
    )
    (net (code "33") (name "/MAG_TXA_A_N") (class "Default")
      (node (ref "J2") (pin "2") (pinfunction "2_2") (pintype "passive"))
    )
    (net (code "34") (name "/MAG_TXA_A_P") (class "Default")
      (node (ref "J2") (pin "1") (pinfunction "1_1") (pintype "passive"))
    )
    (net (code "35") (name "/MAG_TXA_B_N") (class "Default")
      (node (ref "C125") (pin "2") (pinfunction "2_2") (pintype "passive"))
    )
    (net (code "36") (name "/MAG_TXA_B_P") (class "Default")
      (node (ref "C124") (pin "2") (pinfunction "2_2") (pintype "passive"))
    )
    (net (code "37") (name "/MAG_TXA_C_N") (class "Default")
      (node (ref "C129") (pin "1") (pinfunction "1_1") (pintype "passive"))
    )
    (net (code "38") (name "/MAG_TXA_C_P") (class "Default")
      (node (ref "C128") (pin "1") (pinfunction "1_1") (pintype "passive"))
    )
    (net (code "39") (name "/MAG_TXA_D_N") (class "Default")
      (node (ref "J5") (pin "2") (pinfunction "2_2") (pintype "passive"))
    )
    (net (code "40") (name "/MAG_TXA_D_P") (class "Default")
      (node (ref "J5") (pin "1") (pinfunction "1_1") (pintype "passive"))
    )
    (net (code "41") (name "/MAG_TXB_A_N") (class "Default")
      (node (ref "J3") (pin "2") (pinfunction "2_2") (pintype "passive"))
    )
    (net (code "42") (name "/MAG_TXB_A_P") (class "Default")
      (node (ref "J3") (pin "1") (pinfunction "1_1") (pintype "passive"))
    )
    (net (code "43") (name "/MAG_TXB_B_N") (class "Default")
      (node (ref "J4") (pin "2") (pinfunction "2_2") (pintype "passive"))
    )
    (net (code "44") (name "/MAG_TXB_B_P") (class "Default")
      (node (ref "J4") (pin "1") (pinfunction "1_1") (pintype "passive"))
    )
    (net (code "45") (name "/MAG_TXB_C_N") (class "Default")
      (node (ref "J6") (pin "2") (pinfunction "2_2") (pintype "passive"))
    )
    (net (code "46") (name "/MAG_TXB_C_P") (class "Default")
      (node (ref "J6") (pin "1") (pinfunction "1_1") (pintype "passive"))
    )
    (net (code "47") (name "/MAG_TXB_D_N") (class "Default")
      (node (ref "J7") (pin "2") (pinfunction "2_2") (pintype "passive"))
    )
    (net (code "48") (name "/MAG_TXB_D_P") (class "Default")
      (node (ref "J7") (pin "1") (pinfunction "1_1") (pintype "passive"))
    )
    (net (code "53") (name "/MDIO_A") (class "Default")
      (node (ref "R34") (pin "1") (pinfunction "1_1") (pintype "passive"))
    )
    (net (code "54") (name "/MDIO_B") (class "Default")
      (node (ref "R99") (pin "2") (pinfunction "2_2") (pintype "passive"))
    )
    (net (code "55") (name "/MDIO_C") (class "Default")
      (node (ref "R234") (pin "2") (pinfunction "2_2") (pintype "passive"))
    )
    (net (code "56") (name "/MDIO_D") (class "Default")
      (node (ref "R157") (pin "1") (pinfunction "1_1") (pintype "passive"))
    )
    (net (code "58") (name "/RXCLK_A") (class "Default")
      (node (ref "R259") (pin "1") (pinfunction "1_1") (pintype "passive"))
      (node (ref "R323") (pin "1") (pinfunction "1_1") (pintype "passive"))
    )
    (net (code "59") (name "/RXCLK_B") (class "Default")
      (node (ref "R282") (pin "1") (pinfunction "1_1") (pintype "passive"))
      (node (ref "R324") (pin "2") (pinfunction "2_2") (pintype "passive"))
    )
    (net (code "60") (name "/RXCLK_C") (class "Default")
      (node (ref "R320") (pin "1") (pinfunction "1_1") (pintype "passive"))
      (node (ref "R326") (pin "2") (pinfunction "2_2") (pintype "passive"))
    )
    (net (code "61") (name "/RXCLK_D") (class "Default")
      (node (ref "R292") (pin "1") (pinfunction "1_1") (pintype "passive"))
      (node (ref "R325") (pin "1") (pinfunction "1_1") (pintype "passive"))
    )
    (net (code "62") (name "/RXD0_A") (class "Default")
      (node (ref "R59") (pin "1") (pinfunction "1_1") (pintype "passive"))
      (node (ref "R62") (pin "1") (pinfunction "1_1") (pintype "passive"))
    )
    (net (code "63") (name "/RXD0_B") (class "Default")
      (node (ref "R70") (pin "2") (pinfunction "2_2") (pintype "passive"))
      (node (ref "R74") (pin "1") (pinfunction "1_1") (pintype "passive"))
    )
    (net (code "64") (name "/RXD0_C") (class "Default")
      (node (ref "R192") (pin "2") (pinfunction "2_2") (pintype "passive"))
      (node (ref "R195") (pin "1") (pinfunction "1_1") (pintype "passive"))
    )
    (net (code "65") (name "/RXD0_D") (class "Default")
      (node (ref "R181") (pin "1") (pinfunction "1_1") (pintype "passive"))
      (node (ref "R185") (pin "1") (pinfunction "1_1") (pintype "passive"))
    )
    (net (code "66") (name "/RXD1_A") (class "Default")
      (node (ref "R55") (pin "1") (pinfunction "1_1") (pintype "passive"))
      (node (ref "R57") (pin "1") (pinfunction "1_1") (pintype "passive"))
    )
    (net (code "67") (name "/RXD1_B") (class "Default")
      (node (ref "R76") (pin "2") (pinfunction "2_2") (pintype "passive"))
      (node (ref "R79") (pin "1") (pinfunction "1_1") (pintype "passive"))
    )
    (net (code "68") (name "/RXD1_C") (class "Default")
      (node (ref "R199") (pin "2") (pinfunction "2_2") (pintype "passive"))
      (node (ref "R202") (pin "1") (pinfunction "1_1") (pintype "passive"))
    )
    (net (code "69") (name "/RXD1_D") (class "Default")
      (node (ref "R176") (pin "1") (pinfunction "1_1") (pintype "passive"))
      (node (ref "R178") (pin "1") (pinfunction "1_1") (pintype "passive"))
    )
    (net (code "70") (name "/RXD2_A") (class "Default")
      (node (ref "R43") (pin "1") (pinfunction "1_1") (pintype "passive"))
      (node (ref "R44") (pin "1") (pinfunction "1_1") (pintype "passive"))
      (node (ref "R45") (pin "1") (pinfunction "1_1") (pintype "passive"))
    )
    (net (code "71") (name "/RXD2_B") (class "Default")
      (node (ref "R84") (pin "2") (pinfunction "2_2") (pintype "passive"))
      (node (ref "R88") (pin "2") (pinfunction "2_2") (pintype "passive"))
      (node (ref "R92") (pin "1") (pinfunction "1_1") (pintype "passive"))
    )
    (net (code "72") (name "/RXD2_C") (class "Default")
      (node (ref "R211") (pin "2") (pinfunction "2_2") (pintype "passive"))
      (node (ref "R218") (pin "2") (pinfunction "2_2") (pintype "passive"))
      (node (ref "R224") (pin "1") (pinfunction "1_1") (pintype "passive"))
    )
    (net (code "73") (name "/RXD2_D") (class "Default")
      (node (ref "R164") (pin "1") (pinfunction "1_1") (pintype "passive"))
      (node (ref "R165") (pin "1") (pinfunction "1_1") (pintype "passive"))
      (node (ref "R166") (pin "1") (pinfunction "1_1") (pintype "passive"))
    )
    (net (code "74") (name "/RXD3_A") (class "Default")
      (node (ref "R20") (pin "1") (pinfunction "1_1") (pintype "passive"))
      (node (ref "R23") (pin "1") (pinfunction "1_1") (pintype "passive"))
      (node (ref "R24") (pin "1") (pinfunction "1_1") (pintype "passive"))
    )
    (net (code "75") (name "/RXD3_B") (class "Default")
      (node (ref "R103") (pin "2") (pinfunction "2_2") (pintype "passive"))
      (node (ref "R104") (pin "2") (pinfunction "2_2") (pintype "passive"))
      (node (ref "R114") (pin "1") (pinfunction "1_1") (pintype "passive"))
    )
    (net (code "76") (name "/RXD3_C") (class "Default")
      (node (ref "R243") (pin "2") (pinfunction "2_2") (pintype "passive"))
      (node (ref "R244") (pin "2") (pinfunction "2_2") (pintype "passive"))
      (node (ref "R250") (pin "1") (pinfunction "1_1") (pintype "passive"))
    )
    (net (code "77") (name "/RXD3_D") (class "Default")
      (node (ref "R139") (pin "1") (pinfunction "1_1") (pintype "passive"))
      (node (ref "R142") (pin "1") (pinfunction "1_1") (pintype "passive"))
      (node (ref "R145") (pin "1") (pinfunction "1_1") (pintype "passive"))
    )
    (net (code "78") (name "/RXDV_A") (class "Default")
      (node (ref "R64") (pin "1") (pinfunction "1_1") (pintype "passive"))
      (node (ref "R65") (pin "1") (pinfunction "1_1") (pintype "passive"))
    )
    (net (code "79") (name "/RXDV_B") (class "Default")
      (node (ref "R66") (pin "2") (pinfunction "2_2") (pintype "passive"))
      (node (ref "R67") (pin "1") (pinfunction "1_1") (pintype "passive"))
    )
    (net (code "80") (name "/RXDV_C") (class "Default")
      (node (ref "R189") (pin "2") (pinfunction "2_2") (pintype "passive"))
      (node (ref "R191") (pin "1") (pinfunction "1_1") (pintype "passive"))
    )
    (net (code "81") (name "/RXDV_D") (class "Default")
      (node (ref "R186") (pin "1") (pinfunction "1_1") (pintype "passive"))
      (node (ref "R188") (pin "1") (pinfunction "1_1") (pintype "passive"))
    )
    (net (code "82") (name "/RXER_A") (class "Default")
      (node (ref "R25") (pin "1") (pinfunction "1_1") (pintype "passive"))
    )
    (net (code "83") (name "/RXER_B") (class "Default")
      (node (ref "R91") (pin "2") (pinfunction "2_2") (pintype "passive"))
    )
    (net (code "84") (name "/RXER_C") (class "Default")
      (node (ref "R222") (pin "2") (pinfunction "2_2") (pintype "passive"))
    )
    (net (code "85") (name "/RXER_D") (class "Default")
      (node (ref "R148") (pin "1") (pinfunction "1_1") (pintype "passive"))
    )
    (net (code "86") (name "/TXCLK_A") (class "Default")
      (node (ref "R324") (pin "1") (pinfunction "1_1") (pintype "passive"))
    )
    (net (code "87") (name "/TXCLK_B") (class "Default")
      (node (ref "R323") (pin "2") (pinfunction "2_2") (pintype "passive"))
    )
    (net (code "88") (name "/TXCLK_C") (class "Default")
      (node (ref "R325") (pin "2") (pinfunction "2_2") (pintype "passive"))
    )
    (net (code "89") (name "/TXCLK_D") (class "Default")
      (node (ref "R326") (pin "1") (pinfunction "1_1") (pintype "passive"))
    )
    (net (code "90") (name "/TXD0_A") (class "Default")
      (node (ref "R70") (pin "1") (pinfunction "1_1") (pintype "passive"))
    )
    (net (code "91") (name "/TXD0_B") (class "Default")
      (node (ref "R62") (pin "2") (pinfunction "2_2") (pintype "passive"))
    )
    (net (code "92") (name "/TXD0_C") (class "Default")
      (node (ref "R185") (pin "2") (pinfunction "2_2") (pintype "passive"))
    )
    (net (code "93") (name "/TXD0_D") (class "Default")
      (node (ref "R192") (pin "1") (pinfunction "1_1") (pintype "passive"))
    )
    (net (code "94") (name "/TXD1_A") (class "Default")
      (node (ref "R76") (pin "1") (pinfunction "1_1") (pintype "passive"))
    )
    (net (code "95") (name "/TXD1_B") (class "Default")
      (node (ref "R57") (pin "2") (pinfunction "2_2") (pintype "passive"))
    )
    (net (code "96") (name "/TXD1_C") (class "Default")
      (node (ref "R178") (pin "2") (pinfunction "2_2") (pintype "passive"))
    )
    (net (code "97") (name "/TXD1_D") (class "Default")
      (node (ref "R199") (pin "1") (pinfunction "1_1") (pintype "passive"))
    )
    (net (code "98") (name "/TXD2_A") (class "Default")
      (node (ref "R88") (pin "1") (pinfunction "1_1") (pintype "passive"))
    )
    (net (code "99") (name "/TXD2_B") (class "Default")
      (node (ref "R44") (pin "2") (pinfunction "2_2") (pintype "passive"))
    )
    (net (code "100") (name "/TXD2_C") (class "Default")
      (node (ref "R165") (pin "2") (pinfunction "2_2") (pintype "passive"))
    )
    (net (code "101") (name "/TXD2_D") (class "Default")
      (node (ref "R218") (pin "1") (pinfunction "1_1") (pintype "passive"))
    )
    (net (code "102") (name "/TXD3_A") (class "Default")
      (node (ref "R103") (pin "1") (pinfunction "1_1") (pintype "passive"))
    )
    (net (code "103") (name "/TXD3_B") (class "Default")
      (node (ref "R24") (pin "2") (pinfunction "2_2") (pintype "passive"))
    )
    (net (code "104") (name "/TXD3_C") (class "Default")
      (node (ref "R145") (pin "2") (pinfunction "2_2") (pintype "passive"))
    )
    (net (code "105") (name "/TXD3_D") (class "Default")
      (node (ref "R244") (pin "1") (pinfunction "1_1") (pintype "passive"))
    )
    (net (code "106") (name "/TXEN_A") (class "Default")
      (node (ref "R66") (pin "1") (pinfunction "1_1") (pintype "passive"))
    )
    (net (code "107") (name "/TXEN_B") (class "Default")
      (node (ref "R65") (pin "2") (pinfunction "2_2") (pintype "passive"))
    )
    (net (code "108") (name "/TXEN_C") (class "Default")
      (node (ref "R188") (pin "2") (pinfunction "2_2") (pintype "passive"))
    )
    (net (code "109") (name "/TXEN_D") (class "Default")
      (node (ref "R189") (pin "1") (pinfunction "1_1") (pintype "passive"))
    )
    (net (code "110") (name "3V3") (class "Default")
      (node (ref "R101") (pin "2") (pinfunction "2_2") (pintype "passive"))
      (node (ref "R114") (pin "2") (pinfunction "2_2") (pintype "passive"))
      (node (ref "R142") (pin "2") (pinfunction "2_2") (pintype "passive"))
      (node (ref "R155") (pin "2") (pinfunction "2_2") (pintype "passive"))
      (node (ref "R157") (pin "2") (pinfunction "2_2") (pintype "passive"))
      (node (ref "R164") (pin "2") (pinfunction "2_2") (pintype "passive"))
      (node (ref "R171") (pin "2") (pinfunction "2_2") (pintype "passive"))
      (node (ref "R172") (pin "2") (pinfunction "2_2") (pintype "passive"))
      (node (ref "R176") (pin "2") (pinfunction "2_2") (pintype "passive"))
      (node (ref "R181") (pin "2") (pinfunction "2_2") (pintype "passive"))
      (node (ref "R182") (pin "2") (pinfunction "2_2") (pintype "passive"))
      (node (ref "R186") (pin "2") (pinfunction "2_2") (pintype "passive"))
      (node (ref "R191") (pin "2") (pinfunction "2_2") (pintype "passive"))
      (node (ref "R194") (pin "1") (pinfunction "1_1") (pintype "passive"))
      (node (ref "R195") (pin "2") (pinfunction "2_2") (pintype "passive"))
      (node (ref "R202") (pin "2") (pinfunction "2_2") (pintype "passive"))
      (node (ref "R204") (pin "1") (pinfunction "1_1") (pintype "passive"))
      (node (ref "R224") (pin "2") (pinfunction "2_2") (pintype "passive"))
      (node (ref "R23") (pin "2") (pinfunction "2_2") (pintype "passive"))
      (node (ref "R234") (pin "1") (pinfunction "1_1") (pintype "passive"))
      (node (ref "R236") (pin "2") (pinfunction "2_2") (pintype "passive"))
      (node (ref "R250") (pin "2") (pinfunction "2_2") (pintype "passive"))
      (node (ref "R259") (pin "2") (pinfunction "2_2") (pintype "passive"))
      (node (ref "R282") (pin "2") (pinfunction "2_2") (pintype "passive"))
      (node (ref "R292") (pin "2") (pinfunction "2_2") (pintype "passive"))
      (node (ref "R32") (pin "2") (pinfunction "2_2") (pintype "passive"))
      (node (ref "R320") (pin "2") (pinfunction "2_2") (pintype "passive"))
      (node (ref "R34") (pin "2") (pinfunction "2_2") (pintype "passive"))
      (node (ref "R43") (pin "2") (pinfunction "2_2") (pintype "passive"))
      (node (ref "R50") (pin "2") (pinfunction "2_2") (pintype "passive"))
      (node (ref "R55") (pin "2") (pinfunction "2_2") (pintype "passive"))
      (node (ref "R59") (pin "2") (pinfunction "2_2") (pintype "passive"))
      (node (ref "R60") (pin "2") (pinfunction "2_2") (pintype "passive"))
      (node (ref "R64") (pin "2") (pinfunction "2_2") (pintype "passive"))
      (node (ref "R67") (pin "2") (pinfunction "2_2") (pintype "passive"))
      (node (ref "R73") (pin "1") (pinfunction "1_1") (pintype "passive"))
      (node (ref "R74") (pin "2") (pinfunction "2_2") (pintype "passive"))
      (node (ref "R79") (pin "2") (pinfunction "2_2") (pintype "passive"))
      (node (ref "R80") (pin "1") (pinfunction "1_1") (pintype "passive"))
      (node (ref "R82") (pin "2") (pinfunction "2_2") (pintype "passive"))
      (node (ref "R92") (pin "2") (pinfunction "2_2") (pintype "passive"))
      (node (ref "R99") (pin "1") (pinfunction "1_1") (pintype "passive"))
    )
    (net (code "111") (name "GND") (class "Default")
      (node (ref "J2") (pin "3") (pinfunction "3_3") (pintype "passive"))
      (node (ref "J2") (pin "6") (pinfunction "6_6") (pintype "passive"))
      (node (ref "J2") (pin "S1") (pinfunction "SHIELD_S1") (pintype "passive"))
      (node (ref "J2") (pin "S2") (pinfunction "SHIELD_S2") (pintype "passive"))
      (node (ref "J3") (pin "3") (pinfunction "3_3") (pintype "passive"))
      (node (ref "J3") (pin "6") (pinfunction "6_6") (pintype "passive"))
      (node (ref "J3") (pin "S1") (pinfunction "SHIELD_S1") (pintype "passive"))
      (node (ref "J3") (pin "S2") (pinfunction "SHIELD_S2") (pintype "passive"))
      (node (ref "J4") (pin "3") (pinfunction "3_3") (pintype "passive"))
      (node (ref "J4") (pin "6") (pinfunction "6_6") (pintype "passive"))
      (node (ref "J4") (pin "S1") (pinfunction "SHIELD_S1") (pintype "passive"))
      (node (ref "J4") (pin "S2") (pinfunction "SHIELD_S2") (pintype "passive"))
      (node (ref "J5") (pin "3") (pinfunction "3_3") (pintype "passive"))
      (node (ref "J5") (pin "6") (pinfunction "6_6") (pintype "passive"))
      (node (ref "J5") (pin "S1") (pinfunction "SHIELD_S1") (pintype "passive"))
      (node (ref "J5") (pin "S2") (pinfunction "SHIELD_S2") (pintype "passive"))
      (node (ref "J6") (pin "3") (pinfunction "3_3") (pintype "passive"))
      (node (ref "J6") (pin "6") (pinfunction "6_6") (pintype "passive"))
      (node (ref "J6") (pin "S1") (pinfunction "SHIELD_S1") (pintype "passive"))
      (node (ref "J6") (pin "S2") (pinfunction "SHIELD_S2") (pintype "passive"))
      (node (ref "J7") (pin "3") (pinfunction "3_3") (pintype "passive"))
      (node (ref "J7") (pin "6") (pinfunction "6_6") (pintype "passive"))
      (node (ref "J7") (pin "S1") (pinfunction "SHIELD_S1") (pintype "passive"))
      (node (ref "J7") (pin "S2") (pinfunction "SHIELD_S2") (pintype "passive"))
      (node (ref "R104") (pin "1") (pinfunction "1_1") (pintype "passive"))
      (node (ref "R139") (pin "2") (pinfunction "2_2") (pintype "passive"))
      (node (ref "R148") (pin "2") (pinfunction "2_2") (pintype "passive"))
      (node (ref "R166") (pin "2") (pinfunction "2_2") (pintype "passive"))
      (node (ref "R20") (pin "2") (pinfunction "2_2") (pintype "passive"))
      (node (ref "R203") (pin "2") (pinfunction "2_2") (pintype "passive"))
      (node (ref "R211") (pin "1") (pinfunction "1_1") (pintype "passive"))
      (node (ref "R222") (pin "1") (pinfunction "1_1") (pintype "passive"))
      (node (ref "R243") (pin "1") (pinfunction "1_1") (pintype "passive"))
      (node (ref "R25") (pin "2") (pinfunction "2_2") (pintype "passive"))
      (node (ref "R45") (pin "2") (pinfunction "2_2") (pintype "passive"))
      (node (ref "R49") (pin "2") (pinfunction "2_2") (pintype "passive"))
      (node (ref "R84") (pin "1") (pinfunction "1_1") (pintype "passive"))
      (node (ref "R91") (pin "1") (pinfunction "1_1") (pintype "passive"))
    )
  )
)
